# 15_LCD.net
KiCad netlist of a schematic drawn in Altium Designer
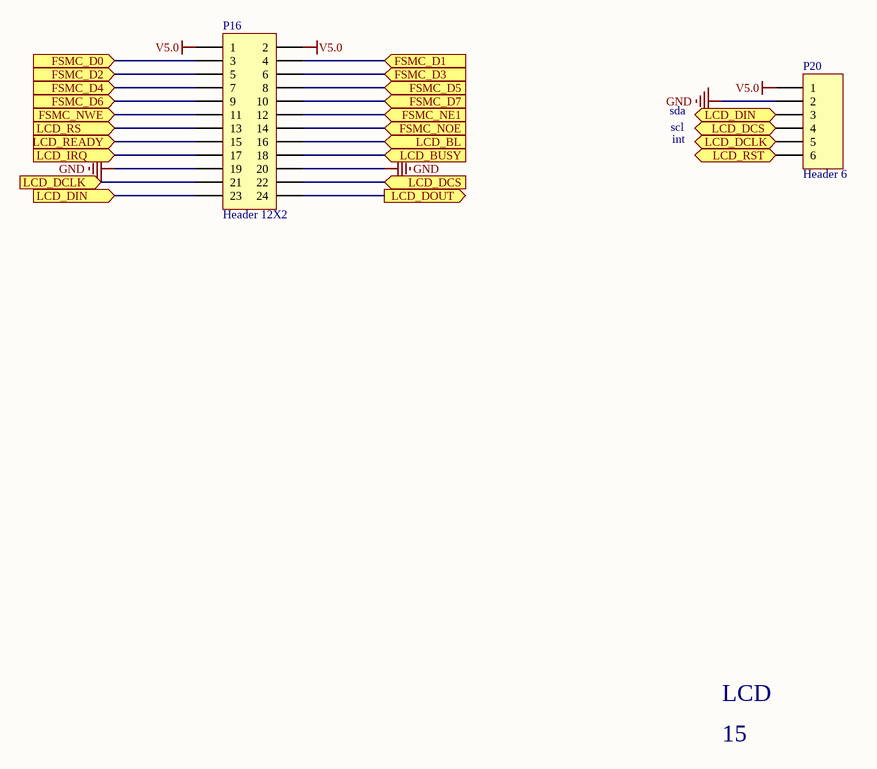
[diagram p0: 15_LCD.SchDoc]

(export (version "E")
  (design (tool "Eeschema 10.0.6"))
  (components
    (comp (ref "P16")
      (value "Header 12X2")
      (footprint "HDR2X12")
      (description "Header, 12-Pin, Dual row")
      (fields (field (name "PUBLISHER") "Altium Limited"))
      (libsource (lib "Miscellaneous Connectors") (part "Header 12X2"))
    )
    (comp (ref "P20")
      (value "Header 6")
      (footprint "HDR1X6")
      (description "Header, 6-Pin")
      (fields (field (name "PUBLISHER") "Altium Limited"))
      (libsource (lib "Miscellaneous Connectors") (part "Header 6"))
    )
  )
  (nets
    (net (code "1") (name "/FSMC_D0") (class "Default")
      (node (ref "P16") (pin "3") (pinfunction "3_3") (pintype "passive"))
    )
    (net (code "2") (name "/FSMC_D1") (class "Default")
      (node (ref "P16") (pin "4") (pinfunction "4_4") (pintype "passive"))
    )
    (net (code "3") (name "/FSMC_D2") (class "Default")
      (node (ref "P16") (pin "5") (pinfunction "5_5") (pintype "passive"))
    )
    (net (code "4") (name "/FSMC_D3") (class "Default")
      (node (ref "P16") (pin "6") (pinfunction "6_6") (pintype "passive"))
    )
    (net (code "5") (name "/FSMC_D4") (class "Default")
      (node (ref "P16") (pin "7") (pinfunction "7_7") (pintype "passive"))
    )
    (net (code "6") (name "/FSMC_D5") (class "Default")
      (node (ref "P16") (pin "8") (pinfunction "8_8") (pintype "passive"))
    )
    (net (code "7") (name "/FSMC_D6") (class "Default")
      (node (ref "P16") (pin "9") (pinfunction "9_9") (pintype "passive"))
    )
    (net (code "8") (name "/FSMC_D7") (class "Default")
      (node (ref "P16") (pin "10") (pinfunction "10_10") (pintype "passive"))
    )
    (net (code "9") (name "/FSMC_NE1") (class "Default")
      (node (ref "P16") (pin "12") (pinfunction "12_12") (pintype "passive"))
    )
    (net (code "10") (name "/FSMC_NOE") (class "Default")
      (node (ref "P16") (pin "14") (pinfunction "14_14") (pintype "passive"))
    )
    (net (code "11") (name "/FSMC_NWE") (class "Default")
      (node (ref "P16") (pin "11") (pinfunction "11_11") (pintype "passive"))
    )
    (net (code "12") (name "/LCD_BL") (class "Default")
      (node (ref "P16") (pin "16") (pinfunction "16_16") (pintype "passive"))
    )
    (net (code "13") (name "/LCD_BUSY") (class "Default")
      (node (ref "P16") (pin "18") (pinfunction "18_18") (pintype "passive"))
    )
    (net (code "14") (name "/LCD_DCLK") (class "Default")
      (node (ref "P16") (pin "21") (pinfunction "21_21") (pintype "passive"))
      (node (ref "P20") (pin "5") (pinfunction "5_5") (pintype "passive"))
    )
    (net (code "15") (name "/LCD_DCS") (class "Default")
      (node (ref "P16") (pin "22") (pinfunction "22_22") (pintype "passive"))
      (node (ref "P20") (pin "4") (pinfunction "4_4") (pintype "passive"))
    )
    (net (code "16") (name "/LCD_DIN") (class "Default")
      (node (ref "P16") (pin "23") (pinfunction "23_23") (pintype "passive"))
      (node (ref "P20") (pin "3") (pinfunction "3_3") (pintype "passive"))
    )
    (net (code "17") (name "/LCD_DOUT") (class "Default")
      (node (ref "P16") (pin "24") (pinfunction "24_24") (pintype "passive"))
    )
    (net (code "18") (name "/LCD_IRQ") (class "Default")
      (node (ref "P16") (pin "17") (pinfunction "17_17") (pintype "passive"))
    )
    (net (code "19") (name "/LCD_READY") (class "Default")
      (node (ref "P16") (pin "15") (pinfunction "15_15") (pintype "passive"))
    )
    (net (code "20") (name "/LCD_RS") (class "Default")
      (node (ref "P16") (pin "13") (pinfunction "13_13") (pintype "passive"))
    )
    (net (code "21") (name "/LCD_RST") (class "Default")
      (node (ref "P20") (pin "6") (pinfunction "6_6") (pintype "passive"))
    )
    (net (code "22") (name "GND") (class "Default")
      (node (ref "P16") (pin "19") (pinfunction "19_19") (pintype "passive"))
      (node (ref "P16") (pin "20") (pinfunction "20_20") (pintype "passive"))
      (node (ref "P20") (pin "2") (pinfunction "2_2") (pintype "passive"))
    )
    (net (code "23") (name "V5.0") (class "Default")
      (node (ref "P16") (pin "1") (pinfunction "1_1") (pintype "passive"))
      (node (ref "P16") (pin "2") (pinfunction "2_2") (pintype "passive"))
      (node (ref "P20") (pin "1") (pinfunction "1_1") (pintype "passive"))
    )
  )
)
